# Microcontroller.net
KiCad netlist of a schematic drawn in Altium Designer
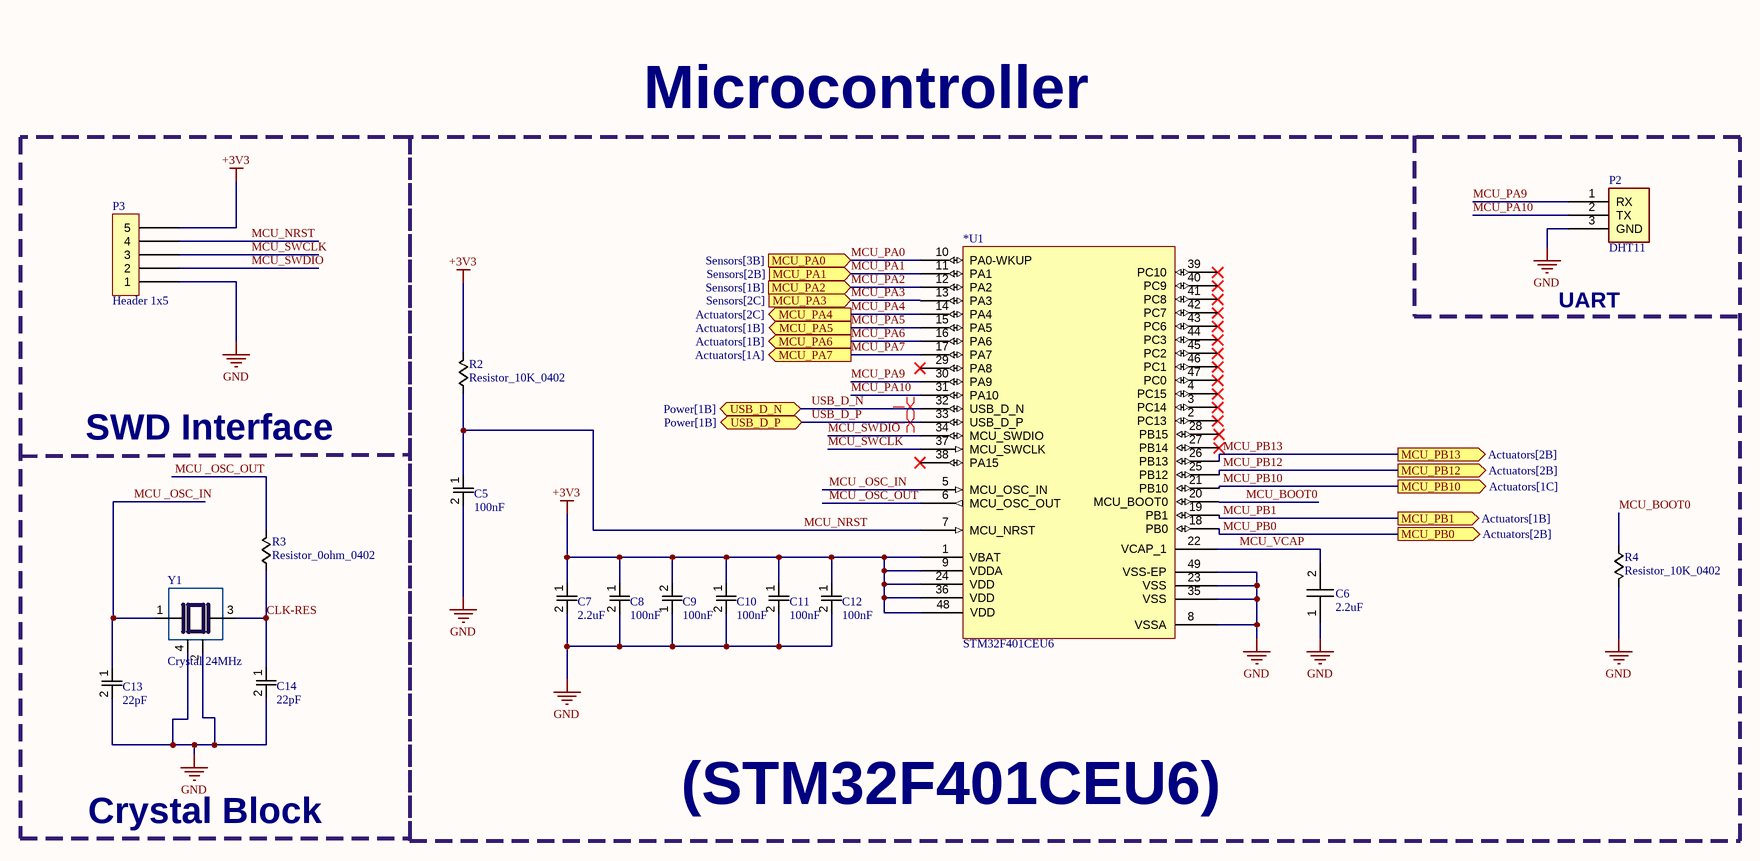
[diagram p0: Microcontroller.SchDoc]

(export (version "E")
  (design (tool "Eeschema 10.0.6"))
  (components
    (comp (ref "*U1")
      (value "STM32F401CEU6")
      (footprint "UFQFPN-48_7x7mm_P0.5mm")
      (description "ARM Cortex-M4 32b MCU+FPU,105DMIPS,512KB Flash/96KB RAM, 11 TIMs, 1 ADC, 11 comm. interfaces")
      (fields (field (name "MANUFACTURER") "ST"))
      (libsource (lib "Microcontroller") (part "STM32F401CEU6"))
    )
    (comp (ref "C5")
      (value "100nF")
      (footprint "CAPC1005X55N")
      (description "CAP CER 100nF 16V X7R 0402")
      (fields
        (field (name "MANUFACTURER") "Samsung Electro-Mechanics")
        (field (name "MANUFACTURER PART #") "CL05B104KO5NNNC")
      )
      (libsource (lib "Microcontroller") (part "Cap_100nF_0402"))
    )
    (comp (ref "C6")
      (value "2.2uF")
      (footprint "CAPC2012X140N")
      (description "CAP CER 2.2uF 16V X7R 0805")
      (fields
        (field (name "MANUFACTURER") "Samsung Electro-Mechanics")
        (field (name "MANUFACTURER PART#") "CL21B225KOFNNNE")
      )
      (libsource (lib "Microcontroller") (part "Cap_0805_2u2F"))
    )
    (comp (ref "C7")
      (value "2.2uF")
      (footprint "CAPC1005X55N")
      (description "CAP CER 2.2uF 16V X5R 0402")
      (fields
        (field (name "MANUFACTURER") "Samsung Electro-Mechanics")
        (field (name "MANUFACTURER PART #") "CL05A225KO5NQNC")
      )
      (libsource (lib "Microcontroller") (part "Cap_2.2uF_0402"))
    )
    (comp (ref "C8")
      (value "100nF")
      (footprint "CAPC1005X55N")
      (description "CAP CER 100nF 16V X7R 0402")
      (fields
        (field (name "MANUFACTURER") "Samsung Electro-Mechanics")
        (field (name "MANUFACTURER PART #") "CL05B104KO5NNNC")
      )
      (libsource (lib "Microcontroller") (part "Cap_100nF_0402"))
    )
    (comp (ref "C9")
      (value "100nF")
      (footprint "CAPC1005X55N")
      (description "CAP CER 100nF 16V X7R 0402")
      (fields
        (field (name "MANUFACTURER") "Samsung Electro-Mechanics")
        (field (name "MANUFACTURER PART #") "CL05B104KO5NNNC")
      )
      (libsource (lib "") (part "Cap_100nF_0402_1"))
    )
    (comp (ref "C10")
      (value "100nF")
      (footprint "CAPC1005X55N")
      (description "CAP CER 100nF 16V X7R 0402")
      (fields
        (field (name "MANUFACTURER") "Samsung Electro-Mechanics")
        (field (name "MANUFACTURER PART #") "CL05B104KO5NNNC")
      )
      (libsource (lib "Microcontroller") (part "Cap_100nF_0402"))
    )
    (comp (ref "C11")
      (value "100nF")
      (footprint "CAPC1005X55N")
      (description "CAP CER 100nF 16V X7R 0402")
      (fields
        (field (name "MANUFACTURER") "Samsung Electro-Mechanics")
        (field (name "MANUFACTURER PART #") "CL05B104KO5NNNC")
      )
      (libsource (lib "Microcontroller") (part "Cap_100nF_0402"))
    )
    (comp (ref "C12")
      (value "100nF")
      (footprint "CAPC1005X55N")
      (description "CAP CER 100nF 16V X7R 0402")
      (fields
        (field (name "MANUFACTURER") "Samsung Electro-Mechanics")
        (field (name "MANUFACTURER PART #") "CL05B104KO5NNNC")
      )
      (libsource (lib "Microcontroller") (part "Cap_100nF_0402"))
    )
    (comp (ref "C13")
      (value "22pF")
      (footprint "CAPC1005X55N")
      (description "CAP CER 22pF 50V NP0 0402")
      (fields (field (name "MANUFACTURER") "YAGEO") (field (name "MANUFACTURER PART #") "CC0402JRNPO9BN220"))
      (libsource (lib "Microcontroller") (part "Cap_22pF_0402"))
    )
    (comp (ref "C14")
      (value "22pF")
      (footprint "CAPC1005X55N")
      (description "CAP CER 22pF 50V NP0 0402")
      (fields (field (name "MANUFACTURER") "YAGEO") (field (name "MANUFACTURER PART #") "CC0402JRNPO9BN220"))
      (libsource (lib "Microcontroller") (part "Cap_22pF_0402"))
    )
    (comp (ref "P2")
      (value "DHT11")
      (footprint "HEADER 1x3 MALE")
      (libsource (lib "Microcontroller") (part "UART"))
    )
    (comp (ref "P3")
      (value "Header 1x5")
      (footprint "Header 1x5 male")
      (libsource (lib "Microcontroller") (part "Header 1x5"))
    )
    (comp (ref "R2")
      (value "Resistor_10K_0402")
      (footprint "RESC1005X40N")
      (description "RES 10kΩ ±1% 62.5mW 0402")
      (fields (field (name "MANUFACTURER") "YAGEO") (field (name "MANUFACTURER PART #") "RC0402FR-0710KL"))
      (libsource (lib "Microcontroller") (part "Resistor_10K_0402"))
    )
    (comp (ref "R3")
      (value "Resistor_0ohm_0402")
      (footprint "RESC1005X40N")
      (description "RES 0Ω 0.1W 0402")
      (fields (field (name "MANUFACTURER") "PANASONIC") (field (name "MANUFACTURER PART #") "ERJ2GE0R00X"))
      (libsource (lib "Microcontroller") (part "Resistor_0ohm_0402"))
    )
    (comp (ref "R4")
      (value "Resistor_10K_0402")
      (footprint "RESC1005X40N")
      (description "RES 10kΩ ±1% 62.5mW 0402")
      (fields (field (name "MANUFACTURER") "YAGEO") (field (name "MANUFACTURER PART #") "RC0402FR-0710KL"))
      (libsource (lib "Microcontroller") (part "Resistor_10K_0402"))
    )
    (comp (ref "Y1")
      (value "Crystal 24MHz")
      (footprint "XTAL_C7S-24.000-12-3030-X-R")
      (description "YXC Crystal Oscillators XL7EL89CKI-111YLC-24M")
      (fields
        (field (name "MANUFACTURER") "YXC Crystal Oscillators")
        (field (name "MANUFACTURER PART#") "SMD2016-4P")
      )
      (libsource (lib "Microcontroller") (part "Crystal 24MHz"))
    )
  )
  (nets
    (net (code "1") (name "+3V3") (class "Default")
      (node (ref "*U1") (pin "1") (pinfunction "VBAT_1") (pintype "power_in"))
      (node (ref "*U1") (pin "24") (pinfunction "VDD_24") (pintype "power_in"))
      (node (ref "*U1") (pin "36") (pinfunction "VDD_36") (pintype "power_in"))
      (node (ref "*U1") (pin "48") (pinfunction "VDD_48") (pintype "power_in"))
      (node (ref "*U1") (pin "9") (pinfunction "VDDA_9") (pintype "power_in"))
      (node (ref "C10") (pin "1") (pinfunction "1_1") (pintype "passive"))
      (node (ref "C11") (pin "1") (pinfunction "1_1") (pintype "passive"))
      (node (ref "C12") (pin "1") (pinfunction "1_1") (pintype "passive"))
      (node (ref "C7") (pin "1") (pinfunction "1_1") (pintype "passive"))
      (node (ref "C8") (pin "1") (pinfunction "1_1") (pintype "passive"))
      (node (ref "C9") (pin "2") (pinfunction "2_2") (pintype "passive"))
      (node (ref "P3") (pin "5") (pinfunction "5_5") (pintype "passive"))
      (node (ref "R2") (pin "2") (pinfunction "2_2") (pintype "passive"))
    )
    (net (code "2") (name "/CLK-RES") (class "Default")
      (node (ref "C14") (pin "1") (pinfunction "1_1") (pintype "passive"))
      (node (ref "R3") (pin "1") (pinfunction "1_1") (pintype "passive"))
      (node (ref "Y1") (pin "3") (pinfunction "2_3") (pintype "passive"))
    )
    (net (code "3") (name "/MCU _OSC_IN") (class "Default")
      (node (ref "*U1") (pin "5") (pinfunction "MCU_OSC_IN_5") (pintype "input"))
      (node (ref "C13") (pin "1") (pinfunction "1_1") (pintype "passive"))
      (node (ref "Y1") (pin "1") (pinfunction "1_1") (pintype "passive"))
    )
    (net (code "4") (name "/MCU _OSC_OUT") (class "Default")
      (node (ref "*U1") (pin "6") (pinfunction "MCU_OSC_OUT_6") (pintype "output"))
      (node (ref "R3") (pin "2") (pinfunction "2_2") (pintype "passive"))
    )
    (net (code "5") (name "/MCU_BOOT0") (class "Default")
      (node (ref "*U1") (pin "20") (pinfunction "MCU_BOOT0_20") (pintype "bidirectional"))
      (node (ref "R4") (pin "1") (pinfunction "1_1") (pintype "passive"))
    )
    (net (code "6") (name "/MCU_NRST") (class "Default")
      (node (ref "*U1") (pin "7") (pinfunction "MCU_NRST_7") (pintype "input"))
      (node (ref "C5") (pin "1") (pinfunction "1_1") (pintype "passive"))
      (node (ref "P3") (pin "4") (pinfunction "4_4") (pintype "passive"))
      (node (ref "R2") (pin "1") (pinfunction "1_1") (pintype "passive"))
    )
    (net (code "7") (name "/MCU_PA0") (class "Default")
      (node (ref "*U1") (pin "10") (pinfunction "PA0-WKUP_10") (pintype "bidirectional"))
    )
    (net (code "8") (name "/MCU_PA1") (class "Default")
      (node (ref "*U1") (pin "11") (pinfunction "PA1_11") (pintype "bidirectional"))
    )
    (net (code "9") (name "/MCU_PA2") (class "Default")
      (node (ref "*U1") (pin "12") (pinfunction "PA2_12") (pintype "bidirectional"))
    )
    (net (code "10") (name "/MCU_PA3") (class "Default")
      (node (ref "*U1") (pin "13") (pinfunction "PA3_13") (pintype "bidirectional"))
    )
    (net (code "11") (name "/MCU_PA4") (class "Default")
      (node (ref "*U1") (pin "14") (pinfunction "PA4_14") (pintype "bidirectional"))
    )
    (net (code "12") (name "/MCU_PA5") (class "Default")
      (node (ref "*U1") (pin "15") (pinfunction "PA5_15") (pintype "bidirectional"))
    )
    (net (code "13") (name "/MCU_PA6") (class "Default")
      (node (ref "*U1") (pin "16") (pinfunction "PA6_16") (pintype "bidirectional"))
    )
    (net (code "14") (name "/MCU_PA7") (class "Default")
      (node (ref "*U1") (pin "17") (pinfunction "PA7_17") (pintype "bidirectional"))
    )
    (net (code "15") (name "/MCU_PA9") (class "Default")
      (node (ref "*U1") (pin "30") (pinfunction "PA9_30") (pintype "bidirectional"))
      (node (ref "P2") (pin "1") (pinfunction "RX_1") (pintype "passive"))
    )
    (net (code "16") (name "/MCU_PA10") (class "Default")
      (node (ref "*U1") (pin "31") (pinfunction "PA10_31") (pintype "bidirectional"))
      (node (ref "P2") (pin "2") (pinfunction "TX_2") (pintype "passive"))
    )
    (net (code "17") (name "/MCU_PB0") (class "Default")
      (node (ref "*U1") (pin "18") (pinfunction "PB0_18") (pintype "bidirectional"))
    )
    (net (code "18") (name "/MCU_PB1") (class "Default")
      (node (ref "*U1") (pin "19") (pinfunction "PB1_19") (pintype "bidirectional"))
    )
    (net (code "19") (name "/MCU_PB10") (class "Default")
      (node (ref "*U1") (pin "21") (pinfunction "PB10_21") (pintype "bidirectional"))
    )
    (net (code "20") (name "/MCU_PB12") (class "Default")
      (node (ref "*U1") (pin "25") (pinfunction "PB12_25") (pintype "bidirectional"))
    )
    (net (code "21") (name "/MCU_PB13") (class "Default")
      (node (ref "*U1") (pin "26") (pinfunction "PB13_26") (pintype "bidirectional"))
    )
    (net (code "22") (name "/MCU_SWCLK") (class "Default")
      (node (ref "*U1") (pin "37") (pinfunction "MCU_SWCLK_37") (pintype "input"))
      (node (ref "P3") (pin "3") (pinfunction "3_3") (pintype "passive"))
    )
    (net (code "23") (name "/MCU_SWDIO") (class "Default")
      (node (ref "*U1") (pin "34") (pinfunction "MCU_SWDIO_34") (pintype "bidirectional"))
      (node (ref "P3") (pin "2") (pinfunction "2_2") (pintype "passive"))
    )
    (net (code "24") (name "/MCU_VCAP") (class "Default")
      (node (ref "*U1") (pin "22") (pinfunction "VCAP_1_22") (pintype "power_in"))
      (node (ref "C6") (pin "2") (pinfunction "2_2") (pintype "passive"))
    )
    (net (code "25") (name "/USB_D_N") (class "Default")
      (node (ref "*U1") (pin "32") (pinfunction "USB_D_N_32") (pintype "bidirectional"))
    )
    (net (code "26") (name "/USB_D_P") (class "Default")
      (node (ref "*U1") (pin "33") (pinfunction "USB_D_P_33") (pintype "bidirectional"))
    )
    (net (code "27") (name "GND") (class "Default")
      (node (ref "*U1") (pin "23") (pinfunction "VSS_23") (pintype "power_in"))
      (node (ref "*U1") (pin "35") (pinfunction "VSS_35") (pintype "power_in"))
      (node (ref "*U1") (pin "49") (pinfunction "VSS-EP_49") (pintype "power_in"))
      (node (ref "*U1") (pin "8") (pinfunction "VSSA_8") (pintype "power_in"))
      (node (ref "C10") (pin "2") (pinfunction "2_2") (pintype "passive"))
      (node (ref "C11") (pin "2") (pinfunction "2_2") (pintype "passive"))
      (node (ref "C12") (pin "2") (pinfunction "2_2") (pintype "passive"))
      (node (ref "C13") (pin "2") (pinfunction "2_2") (pintype "passive"))
      (node (ref "C14") (pin "2") (pinfunction "2_2") (pintype "passive"))
      (node (ref "C5") (pin "2") (pinfunction "2_2") (pintype "passive"))
      (node (ref "C6") (pin "1") (pinfunction "1_1") (pintype "passive"))
      (node (ref "C7") (pin "2") (pinfunction "2_2") (pintype "passive"))
      (node (ref "C8") (pin "2") (pinfunction "2_2") (pintype "passive"))
      (node (ref "C9") (pin "1") (pinfunction "1_1") (pintype "passive"))
      (node (ref "P2") (pin "3") (pinfunction "GND_3") (pintype "passive"))
      (node (ref "P3") (pin "1") (pinfunction "1_1") (pintype "passive"))
      (node (ref "R4") (pin "2") (pinfunction "2_2") (pintype "passive"))
      (node (ref "Y1") (pin "2") (pintype "power_in"))
      (node (ref "Y1") (pin "4") (pintype "power_in"))
    )
    (net (code "28") (name "unconnected-(*U1-PA8-Pad29)") (class "Default")
      (node (ref "*U1") (pin "29") (pinfunction "PA8_29") (pintype "bidirectional+no_connect"))
    )
    (net (code "29") (name "unconnected-(*U1-PA15-Pad38)") (class "Default")
      (node (ref "*U1") (pin "38") (pinfunction "PA15_38") (pintype "bidirectional+no_connect"))
    )
    (net (code "30") (name "unconnected-(*U1-PB14-Pad27)") (class "Default")
      (node (ref "*U1") (pin "27") (pinfunction "PB14_27") (pintype "bidirectional+no_connect"))
    )
    (net (code "31") (name "unconnected-(*U1-PB15-Pad28)") (class "Default")
      (node (ref "*U1") (pin "28") (pinfunction "PB15_28") (pintype "bidirectional+no_connect"))
    )
    (net (code "32") (name "unconnected-(*U1-PC0-Pad47)") (class "Default")
      (node (ref "*U1") (pin "47") (pinfunction "PC0_47") (pintype "bidirectional+no_connect"))
    )
    (net (code "33") (name "unconnected-(*U1-PC1-Pad46)") (class "Default")
      (node (ref "*U1") (pin "46") (pinfunction "PC1_46") (pintype "bidirectional+no_connect"))
    )
    (net (code "34") (name "unconnected-(*U1-PC2-Pad45)") (class "Default")
      (node (ref "*U1") (pin "45") (pinfunction "PC2_45") (pintype "bidirectional+no_connect"))
    )
    (net (code "35") (name "unconnected-(*U1-PC3-Pad44)") (class "Default")
      (node (ref "*U1") (pin "44") (pinfunction "PC3_44") (pintype "bidirectional+no_connect"))
    )
    (net (code "36") (name "unconnected-(*U1-PC6-Pad43)") (class "Default")
      (node (ref "*U1") (pin "43") (pinfunction "PC6_43") (pintype "bidirectional+no_connect"))
    )
    (net (code "37") (name "unconnected-(*U1-PC7-Pad42)") (class "Default")
      (node (ref "*U1") (pin "42") (pinfunction "PC7_42") (pintype "bidirectional+no_connect"))
    )
    (net (code "38") (name "unconnected-(*U1-PC8-Pad41)") (class "Default")
      (node (ref "*U1") (pin "41") (pinfunction "PC8_41") (pintype "bidirectional+no_connect"))
    )
    (net (code "39") (name "unconnected-(*U1-PC9-Pad40)") (class "Default")
      (node (ref "*U1") (pin "40") (pinfunction "PC9_40") (pintype "bidirectional+no_connect"))
    )
    (net (code "40") (name "unconnected-(*U1-PC10-Pad39)") (class "Default")
      (node (ref "*U1") (pin "39") (pinfunction "PC10_39") (pintype "bidirectional+no_connect"))
    )
    (net (code "41") (name "unconnected-(*U1-PC13-Pad2)") (class "Default")
      (node (ref "*U1") (pin "2") (pinfunction "PC13_2") (pintype "bidirectional+no_connect"))
    )
    (net (code "42") (name "unconnected-(*U1-PC14-Pad3)") (class "Default")
      (node (ref "*U1") (pin "3") (pinfunction "PC14_3") (pintype "bidirectional+no_connect"))
    )
    (net (code "43") (name "unconnected-(*U1-PC15-Pad4)") (class "Default")
      (node (ref "*U1") (pin "4") (pinfunction "PC15_4") (pintype "bidirectional+no_connect"))
    )
  )
)
